# relay.net
KiCad netlist of a schematic drawn in EAGLE
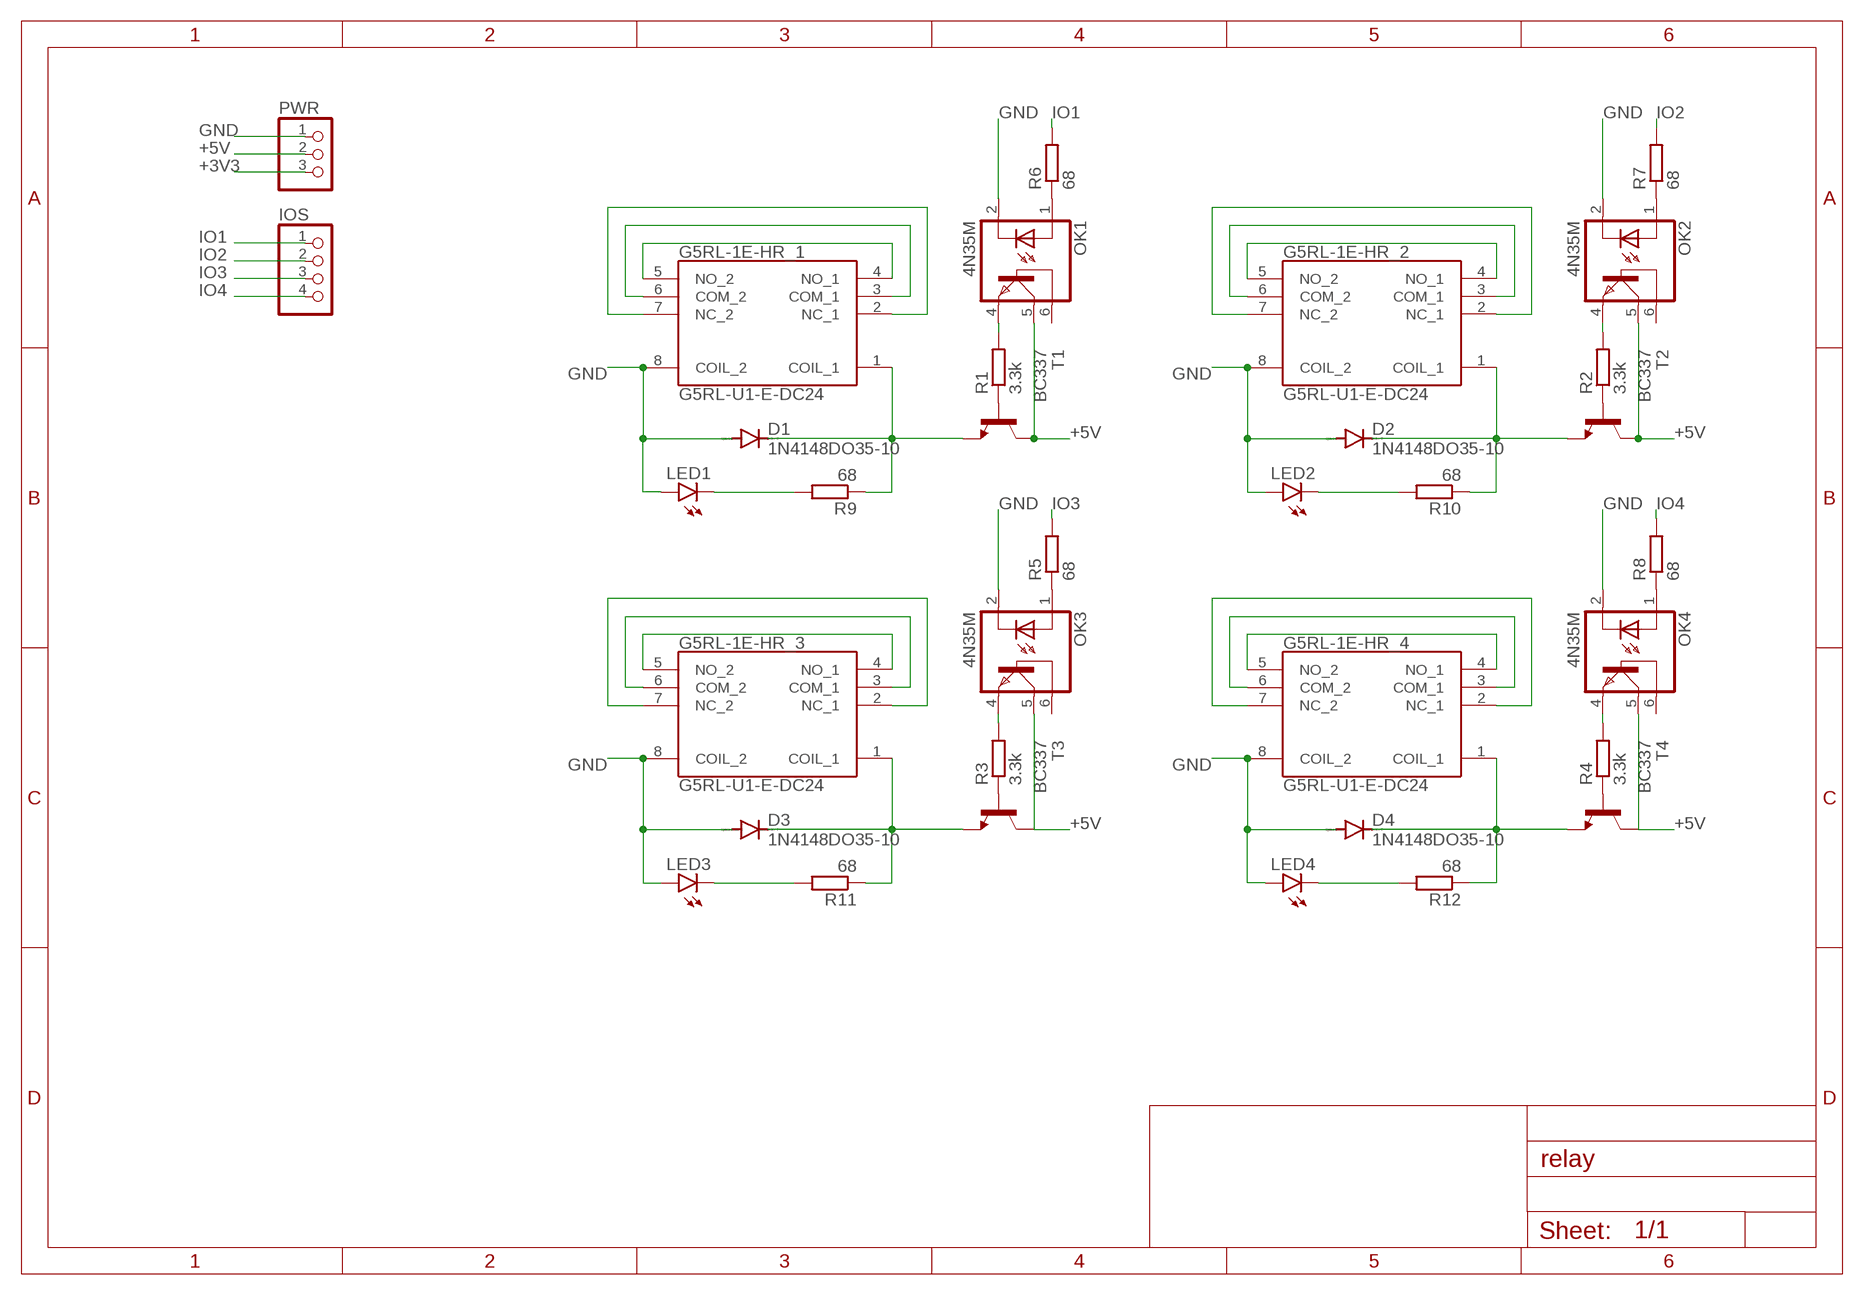
[diagram p0: schematic, sheet 1]

(export (version "E")
  (design (tool "Eeschema 10.0.6"))
  (components
    (comp (ref "D1")
      (value "1N4148DO35-10")
      (footprint "eagle-import:DO35-10")
      (libsource (lib "eagle-import") (part "1N4148DO35-10"))
    )
    (comp (ref "D2")
      (value "1N4148DO35-10")
      (footprint "eagle-import:DO35-10")
      (libsource (lib "eagle-import") (part "1N4148DO35-10"))
    )
    (comp (ref "D3")
      (value "1N4148DO35-10")
      (footprint "eagle-import:DO35-10")
      (libsource (lib "eagle-import") (part "1N4148DO35-10"))
    )
    (comp (ref "D4")
      (value "1N4148DO35-10")
      (footprint "eagle-import:DO35-10")
      (libsource (lib "eagle-import") (part "1N4148DO35-10"))
    )
    (comp (ref "G5RL-1E-HR_1")
      (value "G5RL-U1-E-DC24")
      (footprint "eagle-import:G5RLU1EDC24")
      (fields (field (name "MOUSER_PART_NUMBER") "653-G5RLU1EDC24"))
      (libsource (lib "eagle-import") (part "G5RL-U1-E-DC24"))
    )
    (comp (ref "G5RL-1E-HR_2")
      (value "G5RL-U1-E-DC24")
      (footprint "eagle-import:G5RLU1EDC24")
      (fields (field (name "MOUSER_PART_NUMBER") "653-G5RLU1EDC24"))
      (libsource (lib "eagle-import") (part "G5RL-U1-E-DC24"))
    )
    (comp (ref "G5RL-1E-HR_3")
      (value "G5RL-U1-E-DC24")
      (footprint "eagle-import:G5RLU1EDC24")
      (fields (field (name "MOUSER_PART_NUMBER") "653-G5RLU1EDC24"))
      (libsource (lib "eagle-import") (part "G5RL-U1-E-DC24"))
    )
    (comp (ref "G5RL-1E-HR_4")
      (value "G5RL-U1-E-DC24")
      (footprint "eagle-import:G5RLU1EDC24")
      (fields (field (name "MOUSER_PART_NUMBER") "653-G5RLU1EDC24"))
      (libsource (lib "eagle-import") (part "G5RL-U1-E-DC24"))
    )
    (comp (ref "IOS")
      (value "PINHD-1X4")
      (footprint "eagle-import:1X04")
      (libsource (lib "eagle-import") (part "PINHD-1X4"))
    )
    (comp (ref "LED1")
      (value "LED3MM")
      (footprint "eagle-import:LED3MM")
      (libsource (lib "eagle-import") (part "LED3MM"))
    )
    (comp (ref "LED2")
      (value "LED3MM")
      (footprint "eagle-import:LED3MM")
      (libsource (lib "eagle-import") (part "LED3MM"))
    )
    (comp (ref "LED3")
      (value "LED3MM")
      (footprint "eagle-import:LED3MM")
      (libsource (lib "eagle-import") (part "LED3MM"))
    )
    (comp (ref "LED4")
      (value "LED3MM")
      (footprint "eagle-import:LED3MM")
      (libsource (lib "eagle-import") (part "LED3MM"))
    )
    (comp (ref "OK1")
      (value "4N35M")
      (footprint "eagle-import:DIL06")
      (fields (field (name "MPN") "4N35-M"))
      (libsource (lib "eagle-import") (part "4N?M35"))
    )
    (comp (ref "OK2")
      (value "4N35M")
      (footprint "eagle-import:DIL06")
      (fields (field (name "MPN") "4N35-M"))
      (libsource (lib "eagle-import") (part "4N?M35"))
    )
    (comp (ref "OK3")
      (value "4N35M")
      (footprint "eagle-import:DIL06")
      (fields (field (name "MPN") "4N35-M"))
      (libsource (lib "eagle-import") (part "4N?M35"))
    )
    (comp (ref "OK4")
      (value "4N35M")
      (footprint "eagle-import:DIL06")
      (fields (field (name "MPN") "4N35-M"))
      (libsource (lib "eagle-import") (part "4N?M35"))
    )
    (comp (ref "PWR")
      (value "PINHD-1X3")
      (footprint "eagle-import:1X03")
      (libsource (lib "eagle-import") (part "PINHD-1X3"))
    )
    (comp (ref "R1")
      (value "3.3k")
      (footprint "eagle-import:0207_7")
      (libsource (lib "eagle-import") (part "R-EU_0207/7"))
    )
    (comp (ref "R2")
      (value "3.3k")
      (footprint "eagle-import:0207_7")
      (libsource (lib "eagle-import") (part "R-EU_0207/7"))
    )
    (comp (ref "R3")
      (value "3.3k")
      (footprint "eagle-import:0207_7")
      (libsource (lib "eagle-import") (part "R-EU_0207/7"))
    )
    (comp (ref "R4")
      (value "3.3k")
      (footprint "eagle-import:0207_7")
      (libsource (lib "eagle-import") (part "R-EU_0207/7"))
    )
    (comp (ref "R5")
      (value "68")
      (footprint "eagle-import:0204_7")
      (libsource (lib "eagle-import") (part "R-EU_0204/7"))
    )
    (comp (ref "R6")
      (value "68")
      (footprint "eagle-import:0204_7")
      (libsource (lib "eagle-import") (part "R-EU_0204/7"))
    )
    (comp (ref "R7")
      (value "68")
      (footprint "eagle-import:0204_7")
      (libsource (lib "eagle-import") (part "R-EU_0204/7"))
    )
    (comp (ref "R8")
      (value "68")
      (footprint "eagle-import:0204_7")
      (libsource (lib "eagle-import") (part "R-EU_0204/7"))
    )
    (comp (ref "R9")
      (value "68")
      (footprint "eagle-import:0204_7")
      (libsource (lib "eagle-import") (part "R-EU_0204/7"))
    )
    (comp (ref "R10")
      (value "68")
      (footprint "eagle-import:0204_7")
      (libsource (lib "eagle-import") (part "R-EU_0204/7"))
    )
    (comp (ref "R11")
      (value "68")
      (footprint "eagle-import:0204_7")
      (libsource (lib "eagle-import") (part "R-EU_0204/7"))
    )
    (comp (ref "R12")
      (value "68")
      (footprint "eagle-import:0204_7")
      (libsource (lib "eagle-import") (part "R-EU_0204/7"))
    )
    (comp (ref "T1")
      (value "BC337")
      (footprint "eagle-import:TO92@1")
      (libsource (lib "eagle-import") (part "BC337"))
    )
    (comp (ref "T2")
      (value "BC337")
      (footprint "eagle-import:TO92@1")
      (libsource (lib "eagle-import") (part "BC337"))
    )
    (comp (ref "T3")
      (value "BC337")
      (footprint "eagle-import:TO92@1")
      (libsource (lib "eagle-import") (part "BC337"))
    )
    (comp (ref "T4")
      (value "BC337")
      (footprint "eagle-import:TO92@1")
      (libsource (lib "eagle-import") (part "BC337"))
    )
  )
  (nets
    (net (code "1") (name "/+3V3") (class "Default")
      (node (ref "PWR") (pin "3") (pinfunction "3_3") (pintype "passive"))
    )
    (net (code "2") (name "/+5V") (class "Default")
      (node (ref "OK1") (pin "5") (pinfunction "COL_5") (pintype "passive"))
      (node (ref "OK2") (pin "5") (pinfunction "COL_5") (pintype "passive"))
      (node (ref "OK3") (pin "5") (pinfunction "COL_5") (pintype "passive"))
      (node (ref "OK4") (pin "5") (pinfunction "COL_5") (pintype "passive"))
      (node (ref "PWR") (pin "2") (pinfunction "2_2") (pintype "passive"))
      (node (ref "T1") (pin "3") (pinfunction "C_3") (pintype "passive"))
      (node (ref "T2") (pin "3") (pinfunction "C_3") (pintype "passive"))
      (node (ref "T3") (pin "3") (pinfunction "C_3") (pintype "passive"))
      (node (ref "T4") (pin "3") (pinfunction "C_3") (pintype "passive"))
    )
    (net (code "3") (name "/GND") (class "Default")
      (node (ref "D1") (pin "A") (pinfunction "A_A") (pintype "passive"))
      (node (ref "D2") (pin "A") (pinfunction "A_A") (pintype "passive"))
      (node (ref "D3") (pin "A") (pinfunction "A_A") (pintype "passive"))
      (node (ref "D4") (pin "A") (pinfunction "A_A") (pintype "passive"))
      (node (ref "G5RL-1E-HR_1") (pin "8") (pinfunction "COIL_2_8") (pintype "bidirectional"))
      (node (ref "G5RL-1E-HR_2") (pin "8") (pinfunction "COIL_2_8") (pintype "bidirectional"))
      (node (ref "G5RL-1E-HR_3") (pin "8") (pinfunction "COIL_2_8") (pintype "bidirectional"))
      (node (ref "G5RL-1E-HR_4") (pin "8") (pinfunction "COIL_2_8") (pintype "bidirectional"))
      (node (ref "LED1") (pin "A") (pinfunction "A_A") (pintype "passive"))
      (node (ref "LED2") (pin "A") (pinfunction "A_A") (pintype "passive"))
      (node (ref "LED3") (pin "A") (pinfunction "A_A") (pintype "passive"))
      (node (ref "LED4") (pin "A") (pinfunction "A_A") (pintype "passive"))
      (node (ref "OK1") (pin "2") (pinfunction "C_2") (pintype "passive"))
      (node (ref "OK2") (pin "2") (pinfunction "C_2") (pintype "passive"))
      (node (ref "OK3") (pin "2") (pinfunction "C_2") (pintype "passive"))
      (node (ref "OK4") (pin "2") (pinfunction "C_2") (pintype "passive"))
      (node (ref "PWR") (pin "1") (pinfunction "1_1") (pintype "passive"))
    )
    (net (code "4") (name "/IO1") (class "Default")
      (node (ref "IOS") (pin "1") (pinfunction "1_1") (pintype "passive"))
      (node (ref "R6") (pin "2") (pinfunction "2_2") (pintype "passive"))
    )
    (net (code "5") (name "/IO2") (class "Default")
      (node (ref "IOS") (pin "2") (pinfunction "2_2") (pintype "passive"))
      (node (ref "R7") (pin "2") (pinfunction "2_2") (pintype "passive"))
    )
    (net (code "6") (name "/IO3") (class "Default")
      (node (ref "IOS") (pin "3") (pinfunction "3_3") (pintype "passive"))
      (node (ref "R5") (pin "2") (pinfunction "2_2") (pintype "passive"))
    )
    (net (code "7") (name "/IO4") (class "Default")
      (node (ref "IOS") (pin "4") (pinfunction "4_4") (pintype "passive"))
      (node (ref "R8") (pin "2") (pinfunction "2_2") (pintype "passive"))
    )
    (net (code "8") (name "Net-(G5RL-1E-HR_1-COIL_1)") (class "Default")
      (node (ref "D1") (pin "C") (pinfunction "C_C") (pintype "passive"))
      (node (ref "G5RL-1E-HR_1") (pin "1") (pinfunction "COIL_1_1") (pintype "bidirectional"))
      (node (ref "R9") (pin "1") (pinfunction "1_1") (pintype "passive"))
      (node (ref "T1") (pin "1") (pinfunction "E_1") (pintype "passive"))
    )
    (net (code "9") (name "Net-(G5RL-1E-HR_1-COM_1)") (class "Default")
      (node (ref "G5RL-1E-HR_1") (pin "3") (pinfunction "COM_1_3") (pintype "bidirectional"))
      (node (ref "G5RL-1E-HR_1") (pin "6") (pinfunction "COM_2_6") (pintype "bidirectional"))
    )
    (net (code "10") (name "Net-(G5RL-1E-HR_1-NC_1)") (class "Default")
      (node (ref "G5RL-1E-HR_1") (pin "2") (pinfunction "NC_1_2") (pintype "bidirectional"))
      (node (ref "G5RL-1E-HR_1") (pin "7") (pinfunction "NC_2_7") (pintype "bidirectional"))
    )
    (net (code "11") (name "Net-(G5RL-1E-HR_1-NO_1)") (class "Default")
      (node (ref "G5RL-1E-HR_1") (pin "4") (pinfunction "NO_1_4") (pintype "bidirectional"))
      (node (ref "G5RL-1E-HR_1") (pin "5") (pinfunction "NO_2_5") (pintype "bidirectional"))
    )
    (net (code "12") (name "Net-(G5RL-1E-HR_2-COIL_1)") (class "Default")
      (node (ref "D2") (pin "C") (pinfunction "C_C") (pintype "passive"))
      (node (ref "G5RL-1E-HR_2") (pin "1") (pinfunction "COIL_1_1") (pintype "bidirectional"))
      (node (ref "R10") (pin "1") (pinfunction "1_1") (pintype "passive"))
      (node (ref "T2") (pin "1") (pinfunction "E_1") (pintype "passive"))
    )
    (net (code "13") (name "Net-(G5RL-1E-HR_2-COM_1)") (class "Default")
      (node (ref "G5RL-1E-HR_2") (pin "3") (pinfunction "COM_1_3") (pintype "bidirectional"))
      (node (ref "G5RL-1E-HR_2") (pin "6") (pinfunction "COM_2_6") (pintype "bidirectional"))
    )
    (net (code "14") (name "Net-(G5RL-1E-HR_2-NC_1)") (class "Default")
      (node (ref "G5RL-1E-HR_2") (pin "2") (pinfunction "NC_1_2") (pintype "bidirectional"))
      (node (ref "G5RL-1E-HR_2") (pin "7") (pinfunction "NC_2_7") (pintype "bidirectional"))
    )
    (net (code "15") (name "Net-(G5RL-1E-HR_2-NO_1)") (class "Default")
      (node (ref "G5RL-1E-HR_2") (pin "4") (pinfunction "NO_1_4") (pintype "bidirectional"))
      (node (ref "G5RL-1E-HR_2") (pin "5") (pinfunction "NO_2_5") (pintype "bidirectional"))
    )
    (net (code "16") (name "Net-(G5RL-1E-HR_3-COIL_1)") (class "Default")
      (node (ref "D3") (pin "C") (pinfunction "C_C") (pintype "passive"))
      (node (ref "G5RL-1E-HR_3") (pin "1") (pinfunction "COIL_1_1") (pintype "bidirectional"))
      (node (ref "R11") (pin "1") (pinfunction "1_1") (pintype "passive"))
      (node (ref "T3") (pin "1") (pinfunction "E_1") (pintype "passive"))
    )
    (net (code "17") (name "Net-(G5RL-1E-HR_3-COM_1)") (class "Default")
      (node (ref "G5RL-1E-HR_3") (pin "3") (pinfunction "COM_1_3") (pintype "bidirectional"))
      (node (ref "G5RL-1E-HR_3") (pin "6") (pinfunction "COM_2_6") (pintype "bidirectional"))
    )
    (net (code "18") (name "Net-(G5RL-1E-HR_3-NC_1)") (class "Default")
      (node (ref "G5RL-1E-HR_3") (pin "2") (pinfunction "NC_1_2") (pintype "bidirectional"))
      (node (ref "G5RL-1E-HR_3") (pin "7") (pinfunction "NC_2_7") (pintype "bidirectional"))
    )
    (net (code "19") (name "Net-(G5RL-1E-HR_3-NO_1)") (class "Default")
      (node (ref "G5RL-1E-HR_3") (pin "4") (pinfunction "NO_1_4") (pintype "bidirectional"))
      (node (ref "G5RL-1E-HR_3") (pin "5") (pinfunction "NO_2_5") (pintype "bidirectional"))
    )
    (net (code "20") (name "Net-(G5RL-1E-HR_4-COIL_1)") (class "Default")
      (node (ref "D4") (pin "C") (pinfunction "C_C") (pintype "passive"))
      (node (ref "G5RL-1E-HR_4") (pin "1") (pinfunction "COIL_1_1") (pintype "bidirectional"))
      (node (ref "R12") (pin "1") (pinfunction "1_1") (pintype "passive"))
      (node (ref "T4") (pin "1") (pinfunction "E_1") (pintype "passive"))
    )
    (net (code "21") (name "Net-(G5RL-1E-HR_4-COM_1)") (class "Default")
      (node (ref "G5RL-1E-HR_4") (pin "3") (pinfunction "COM_1_3") (pintype "bidirectional"))
      (node (ref "G5RL-1E-HR_4") (pin "6") (pinfunction "COM_2_6") (pintype "bidirectional"))
    )
    (net (code "22") (name "Net-(G5RL-1E-HR_4-NC_1)") (class "Default")
      (node (ref "G5RL-1E-HR_4") (pin "2") (pinfunction "NC_1_2") (pintype "bidirectional"))
      (node (ref "G5RL-1E-HR_4") (pin "7") (pinfunction "NC_2_7") (pintype "bidirectional"))
    )
    (net (code "23") (name "Net-(G5RL-1E-HR_4-NO_1)") (class "Default")
      (node (ref "G5RL-1E-HR_4") (pin "4") (pinfunction "NO_1_4") (pintype "bidirectional"))
      (node (ref "G5RL-1E-HR_4") (pin "5") (pinfunction "NO_2_5") (pintype "bidirectional"))
    )
    (net (code "24") (name "Net-(LED1-C)") (class "Default")
      (node (ref "LED1") (pin "K") (pinfunction "C_K") (pintype "passive"))
      (node (ref "R9") (pin "2") (pinfunction "2_2") (pintype "passive"))
    )
    (net (code "25") (name "Net-(LED2-C)") (class "Default")
      (node (ref "LED2") (pin "K") (pinfunction "C_K") (pintype "passive"))
      (node (ref "R10") (pin "2") (pinfunction "2_2") (pintype "passive"))
    )
    (net (code "26") (name "Net-(LED3-C)") (class "Default")
      (node (ref "LED3") (pin "K") (pinfunction "C_K") (pintype "passive"))
      (node (ref "R11") (pin "2") (pinfunction "2_2") (pintype "passive"))
    )
    (net (code "27") (name "Net-(LED4-C)") (class "Default")
      (node (ref "LED4") (pin "K") (pinfunction "C_K") (pintype "passive"))
      (node (ref "R12") (pin "2") (pinfunction "2_2") (pintype "passive"))
    )
    (net (code "28") (name "Net-(OK1-A)") (class "Default")
      (node (ref "OK1") (pin "1") (pinfunction "A_1") (pintype "passive"))
      (node (ref "R6") (pin "1") (pinfunction "1_1") (pintype "passive"))
    )
    (net (code "29") (name "Net-(OK1-EMI)") (class "Default")
      (node (ref "OK1") (pin "4") (pinfunction "EMI_4") (pintype "passive"))
      (node (ref "R1") (pin "2") (pinfunction "2_2") (pintype "passive"))
    )
    (net (code "30") (name "Net-(OK2-A)") (class "Default")
      (node (ref "OK2") (pin "1") (pinfunction "A_1") (pintype "passive"))
      (node (ref "R7") (pin "1") (pinfunction "1_1") (pintype "passive"))
    )
    (net (code "31") (name "Net-(OK2-EMI)") (class "Default")
      (node (ref "OK2") (pin "4") (pinfunction "EMI_4") (pintype "passive"))
      (node (ref "R2") (pin "2") (pinfunction "2_2") (pintype "passive"))
    )
    (net (code "32") (name "Net-(OK3-A)") (class "Default")
      (node (ref "OK3") (pin "1") (pinfunction "A_1") (pintype "passive"))
      (node (ref "R5") (pin "1") (pinfunction "1_1") (pintype "passive"))
    )
    (net (code "33") (name "Net-(OK3-EMI)") (class "Default")
      (node (ref "OK3") (pin "4") (pinfunction "EMI_4") (pintype "passive"))
      (node (ref "R3") (pin "2") (pinfunction "2_2") (pintype "passive"))
    )
    (net (code "34") (name "Net-(OK4-A)") (class "Default")
      (node (ref "OK4") (pin "1") (pinfunction "A_1") (pintype "passive"))
      (node (ref "R8") (pin "1") (pinfunction "1_1") (pintype "passive"))
    )
    (net (code "35") (name "Net-(OK4-EMI)") (class "Default")
      (node (ref "OK4") (pin "4") (pinfunction "EMI_4") (pintype "passive"))
      (node (ref "R4") (pin "2") (pinfunction "2_2") (pintype "passive"))
    )
    (net (code "36") (name "Net-(T1-B)") (class "Default")
      (node (ref "R1") (pin "1") (pinfunction "1_1") (pintype "passive"))
      (node (ref "T1") (pin "2") (pinfunction "B_2") (pintype "passive"))
    )
    (net (code "37") (name "Net-(T2-B)") (class "Default")
      (node (ref "R2") (pin "1") (pinfunction "1_1") (pintype "passive"))
      (node (ref "T2") (pin "2") (pinfunction "B_2") (pintype "passive"))
    )
    (net (code "38") (name "Net-(T3-B)") (class "Default")
      (node (ref "R3") (pin "1") (pinfunction "1_1") (pintype "passive"))
      (node (ref "T3") (pin "2") (pinfunction "B_2") (pintype "passive"))
    )
    (net (code "39") (name "Net-(T4-B)") (class "Default")
      (node (ref "R4") (pin "1") (pinfunction "1_1") (pintype "passive"))
      (node (ref "T4") (pin "2") (pinfunction "B_2") (pintype "passive"))
    )
    (net (code "40") (name "unconnected-(OK1-BAS-Pad6)") (class "Default")
      (node (ref "OK1") (pin "6") (pinfunction "BAS_6") (pintype "passive"))
    )
    (net (code "41") (name "unconnected-(OK2-BAS-Pad6)") (class "Default")
      (node (ref "OK2") (pin "6") (pinfunction "BAS_6") (pintype "passive"))
    )
    (net (code "42") (name "unconnected-(OK3-BAS-Pad6)") (class "Default")
      (node (ref "OK3") (pin "6") (pinfunction "BAS_6") (pintype "passive"))
    )
    (net (code "43") (name "unconnected-(OK4-BAS-Pad6)") (class "Default")
      (node (ref "OK4") (pin "6") (pinfunction "BAS_6") (pintype "passive"))
    )
  )
)
